# ControlePotencia.net
KiCad netlist of a schematic drawn in Altium Designer
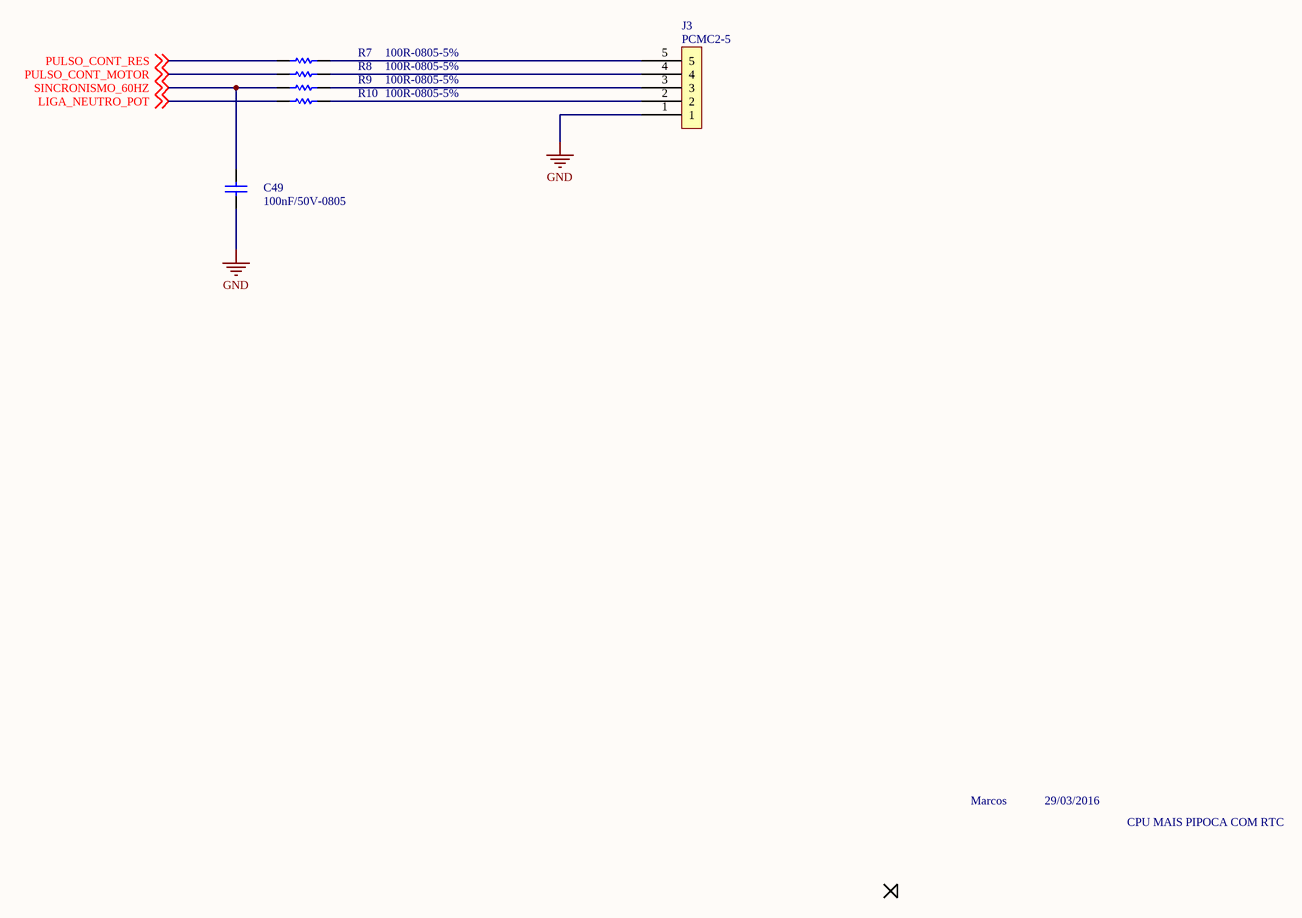
[diagram p0: ControlePotencia.SchDoc]

(export (version "E")
  (design (tool "Eeschema 10.0.6"))
  (components
    (comp (ref "C49")
      (value "100nF/50V-0805")
      (description "100nF/50-0805-NPO")
      (libsource (lib "AquinoLib") (part "100nF/50-0805-NPO"))
    )
    (comp (ref "J3") (value "PCMC2-5") (footprint "PCMC2-5") (libsource (lib "AquinoLib") (part "PCMC2-5")))
    (comp (ref "R7")
      (value "100R-0805-5%")
      (footprint "0805-REVISADO O")
      (libsource (lib "AquinoLib") (part "100R-0805-5%"))
    )
    (comp (ref "R8")
      (value "100R-0805-5%")
      (footprint "0805-REVISADO O")
      (libsource (lib "AquinoLib") (part "100R-0805-5%"))
    )
    (comp (ref "R9")
      (value "100R-0805-5%")
      (footprint "0805-REVISADO O")
      (libsource (lib "AquinoLib") (part "100R-0805-5%"))
    )
    (comp (ref "R10")
      (value "100R-0805-5%")
      (footprint "0805-REVISADO O")
      (libsource (lib "AquinoLib") (part "100R-0805-5%"))
    )
  )
  (nets
    (net (code "1") (name "GND") (class "Default")
      (node (ref "C49") (pin "1") (pinfunction "1_1") (pintype "passive"))
      (node (ref "J3") (pin "1") (pinfunction "1_1") (pintype "passive"))
    )
    (net (code "2") (name "LIGA_NEUTRO_POT") (class "Default")
      (node (ref "R10") (pin "1") (pinfunction "1_1") (pintype "passive"))
    )
    (net (code "3") (name "Net-(J3-Pad2)") (class "Default")
      (node (ref "J3") (pin "2") (pinfunction "2_2") (pintype "passive"))
      (node (ref "R10") (pin "2") (pinfunction "2_2") (pintype "passive"))
    )
    (net (code "4") (name "Net-(J3-Pad3)") (class "Default")
      (node (ref "J3") (pin "3") (pinfunction "3_3") (pintype "passive"))
      (node (ref "R9") (pin "2") (pinfunction "2_2") (pintype "passive"))
    )
    (net (code "5") (name "Net-(J3-Pad4)") (class "Default")
      (node (ref "J3") (pin "4") (pinfunction "4_4") (pintype "passive"))
      (node (ref "R8") (pin "2") (pinfunction "2_2") (pintype "passive"))
    )
    (net (code "6") (name "Net-(J3-Pad5)") (class "Default")
      (node (ref "J3") (pin "5") (pinfunction "5_5") (pintype "passive"))
      (node (ref "R7") (pin "2") (pinfunction "2_2") (pintype "passive"))
    )
    (net (code "7") (name "PULSO_CONT_MOTOR") (class "Default")
      (node (ref "R8") (pin "1") (pinfunction "1_1") (pintype "passive"))
    )
    (net (code "8") (name "PULSO_CONT_RES") (class "Default")
      (node (ref "R7") (pin "1") (pinfunction "1_1") (pintype "passive"))
    )
    (net (code "9") (name "SINCRONISMO_60HZ") (class "Default")
      (node (ref "C49") (pin "2") (pinfunction "2_2") (pintype "passive"))
      (node (ref "R9") (pin "1") (pinfunction "1_1") (pintype "passive"))
    )
  )
)
